# SCH_two-displays_2025-10-05.net
KiCad netlist of a schematic drawn in EasyEDA
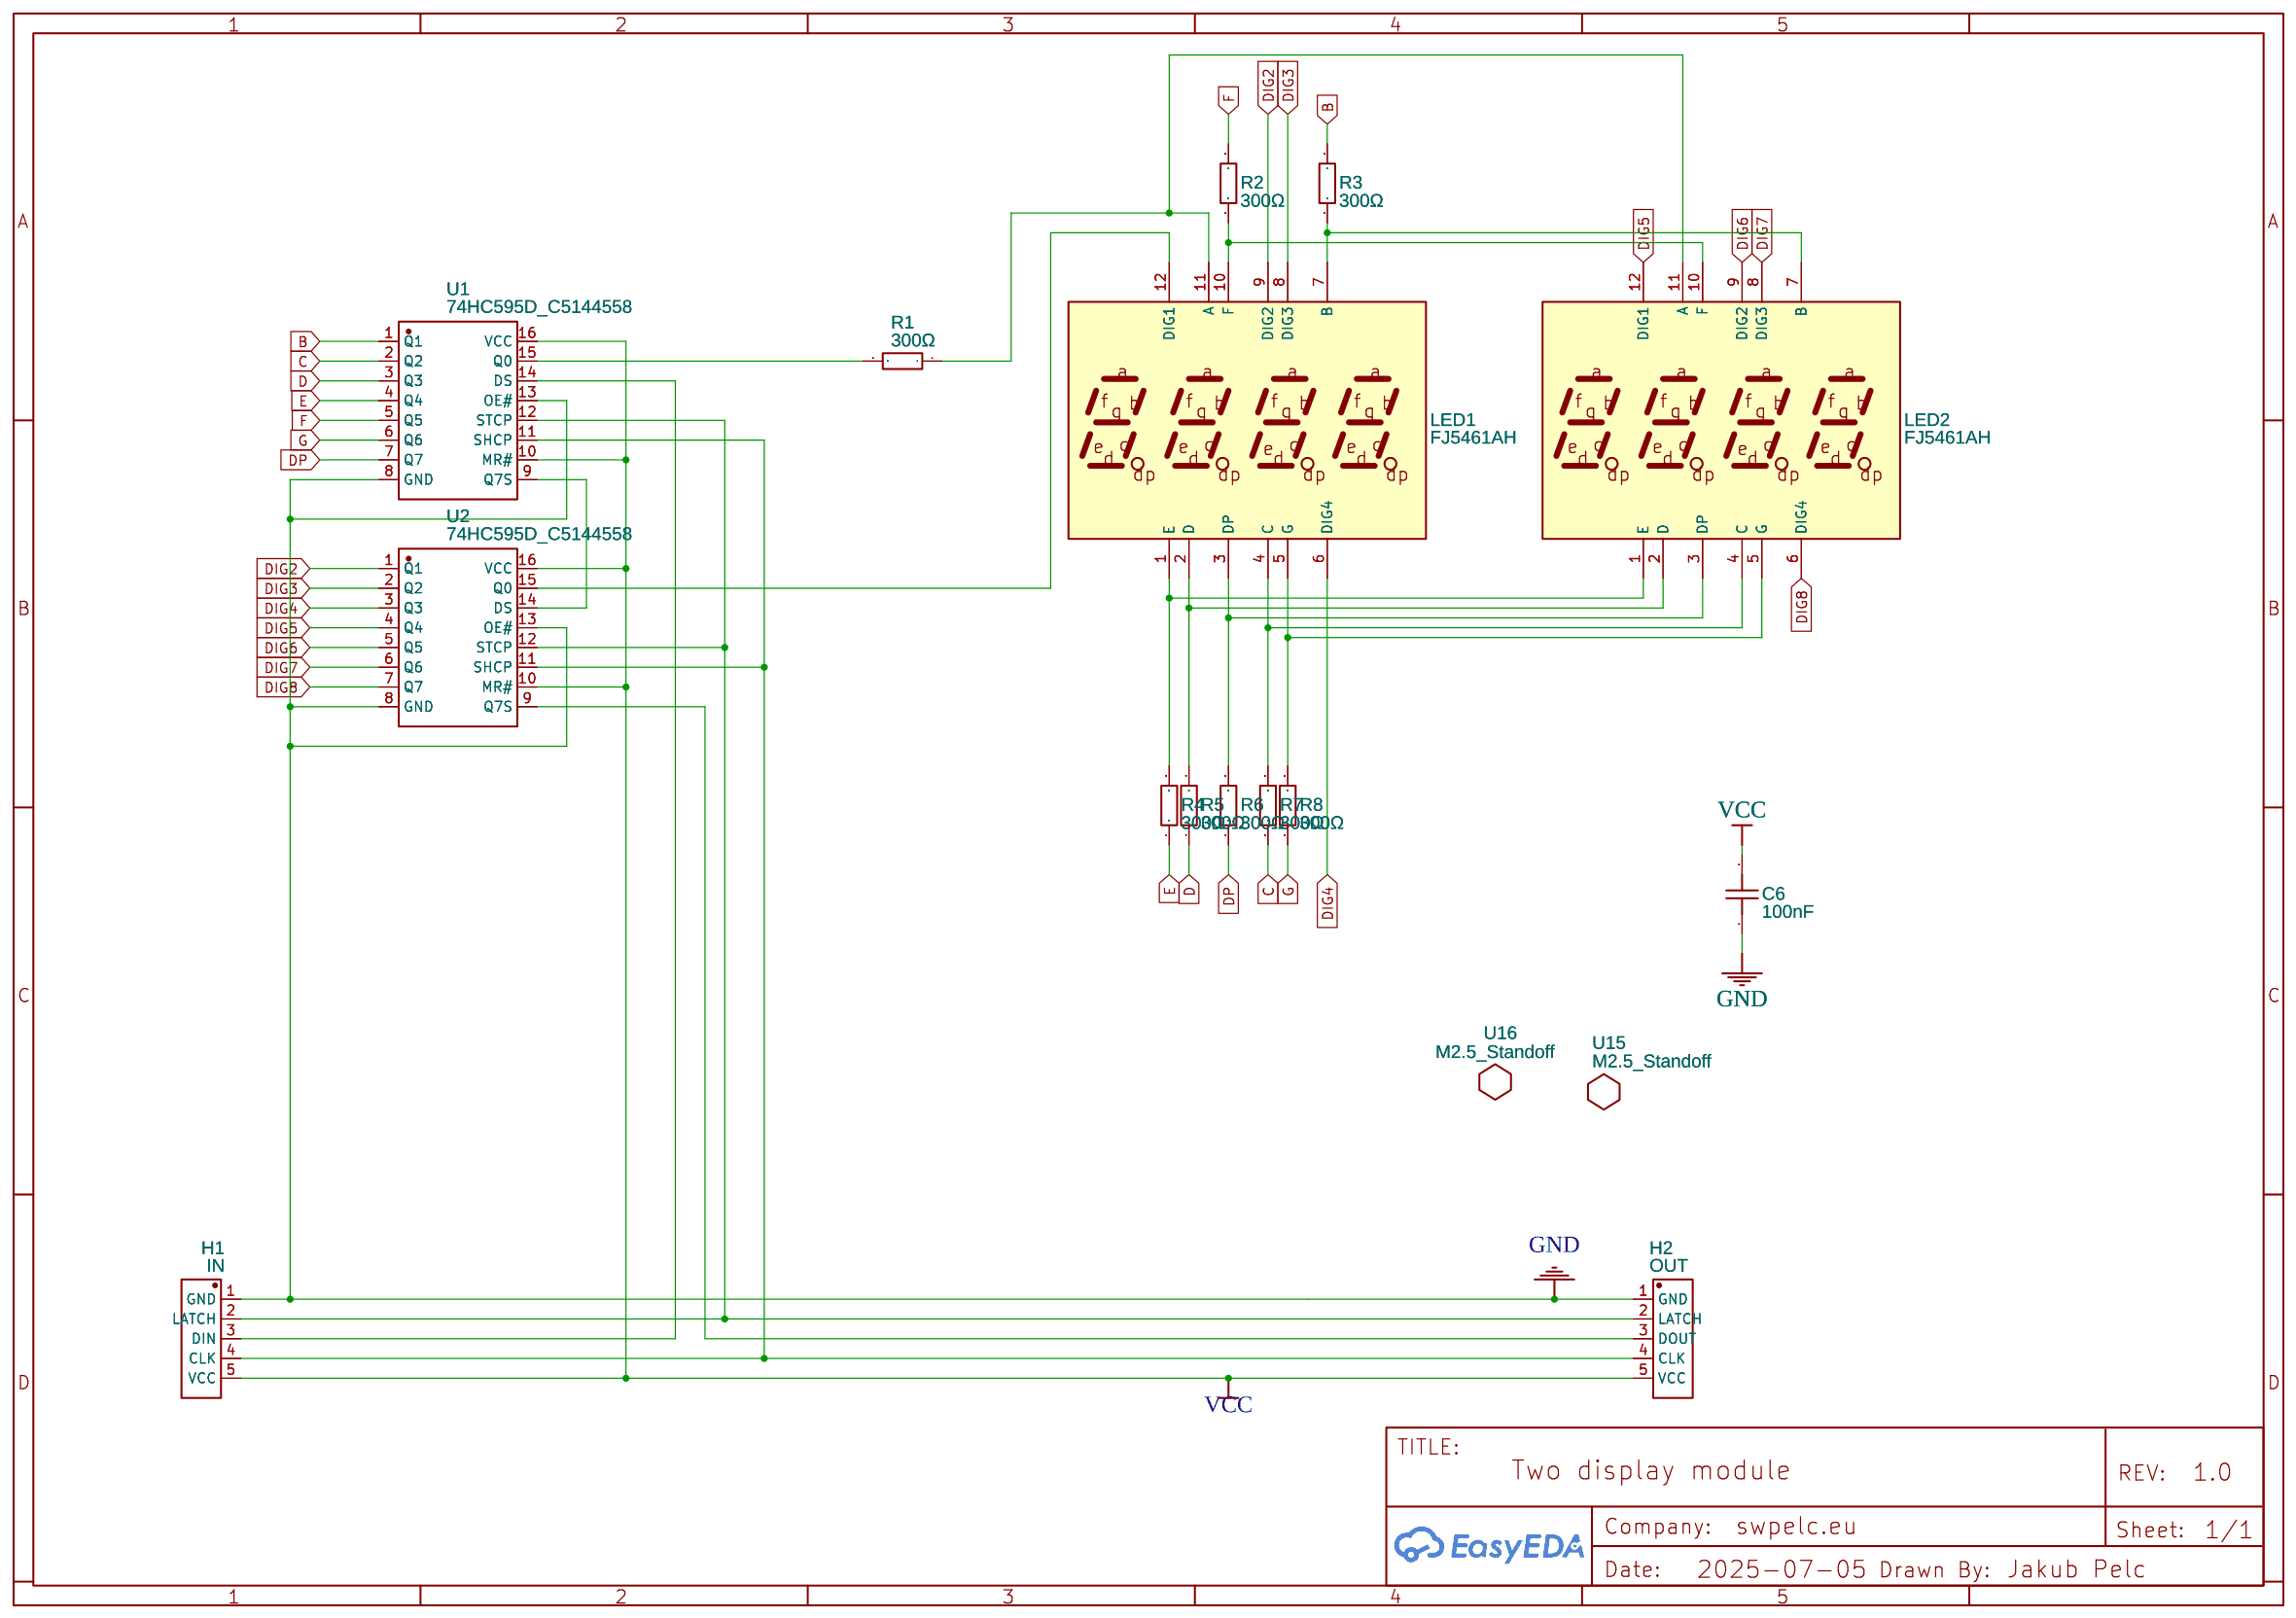
[diagram p0: schematic sheet]

(export (version "E")
  (design (tool "Eeschema 10.0.6"))
  (components
    (comp (ref "C6")
      (value "100nF")
      (fields
        (field (name "Manufacturer Part") "CC0603KRX7R9BB104")
        (field (name "Manufacturer") "YAGEO(国巨)")
      )
      (libsource (lib "") (part "CC0603KRX7R9BB104"))
    )
    (comp (ref "H1") (value "IN") (libsource (lib "") (part "HEADER - 2.54_1X5_1")))
    (comp (ref "H2") (value "OUT") (libsource (lib "") (part "HEADER - 2.54_1X5")))
    (comp (ref "LED1")
      (value "FJ5461AH")
      (fields (field (name "Manufacturer Part") "FJ5461AH 橙红") (field (name "Manufacturer") "志浩"))
      (libsource (lib "") (part "FJ5461AH"))
    )
    (comp (ref "LED2")
      (value "FJ5461AH")
      (fields (field (name "Manufacturer Part") "FJ5461AH 橙红") (field (name "Manufacturer") "志浩"))
      (libsource (lib "") (part "FJ5461AH"))
    )
    (comp (ref "R1")
      (value "300Ω")
      (fields (field (name "Manufacturer Part") "AR03DTC3000") (field (name "Manufacturer") "Viking(光颉)"))
      (libsource (lib "") (part "AR03DTC3000_1"))
    )
    (comp (ref "R2")
      (value "300Ω")
      (fields (field (name "Manufacturer Part") "AR03DTC3000") (field (name "Manufacturer") "Viking(光颉)"))
      (libsource (lib "") (part "AR03DTC3000"))
    )
    (comp (ref "R3")
      (value "300Ω")
      (fields (field (name "Manufacturer Part") "AR03DTC3000") (field (name "Manufacturer") "Viking(光颉)"))
      (libsource (lib "") (part "AR03DTC3000"))
    )
    (comp (ref "R4")
      (value "300Ω")
      (fields (field (name "Manufacturer Part") "AR03DTC3000") (field (name "Manufacturer") "Viking(光颉)"))
      (libsource (lib "") (part "AR03DTC3000"))
    )
    (comp (ref "R5")
      (value "300Ω")
      (fields (field (name "Manufacturer Part") "AR03DTC3000") (field (name "Manufacturer") "Viking(光颉)"))
      (libsource (lib "") (part "AR03DTC3000"))
    )
    (comp (ref "R6")
      (value "300Ω")
      (fields (field (name "Manufacturer Part") "AR03DTC3000") (field (name "Manufacturer") "Viking(光颉)"))
      (libsource (lib "") (part "AR03DTC3000"))
    )
    (comp (ref "R7")
      (value "300Ω")
      (fields (field (name "Manufacturer Part") "AR03DTC3000") (field (name "Manufacturer") "Viking(光颉)"))
      (libsource (lib "") (part "AR03DTC3000"))
    )
    (comp (ref "R8")
      (value "300Ω")
      (fields (field (name "Manufacturer Part") "AR03DTC3000") (field (name "Manufacturer") "Viking(光颉)"))
      (libsource (lib "") (part "AR03DTC3000"))
    )
    (comp (ref "U1")
      (value "74HC595D_C5144558")
      (fields (field (name "Manufacturer Part") "74HC595D") (field (name "Manufacturer") "JSMSEMI(杰盛微)"))
      (libsource (lib "") (part "74HC595D_C5144558"))
    )
    (comp (ref "U2")
      (value "74HC595D_C5144558")
      (fields (field (name "Manufacturer Part") "74HC595D") (field (name "Manufacturer") "JSMSEMI(杰盛微)"))
      (libsource (lib "") (part "74HC595D_C5144558"))
    )
    (comp (ref "U15") (value "M2.5_Standoff") (libsource (lib "") (part "M2.5_Standoff")))
    (comp (ref "U16") (value "M2.5_Standoff") (libsource (lib "") (part "M2.5_Standoff")))
  )
  (nets
    (net (code "1") (name "B") (class "Default")
      (node (ref "R3") (pin "2") (pinfunction "2_2") (pintype "unspecified"))
      (node (ref "U1") (pin "1") (pinfunction "Q1_1") (pintype "unspecified"))
    )
    (net (code "2") (name "C") (class "Default")
      (node (ref "R7") (pin "1") (pinfunction "1_1") (pintype "unspecified"))
      (node (ref "U1") (pin "2") (pinfunction "Q2_2") (pintype "unspecified"))
    )
    (net (code "3") (name "D") (class "Default")
      (node (ref "R5") (pin "1") (pinfunction "1_1") (pintype "unspecified"))
      (node (ref "U1") (pin "3") (pinfunction "Q3_3") (pintype "unspecified"))
    )
    (net (code "4") (name "DIG2") (class "Default")
      (node (ref "LED1") (pin "9") (pinfunction "DIG2_9") (pintype "input"))
      (node (ref "U2") (pin "1") (pinfunction "Q1_1") (pintype "unspecified"))
    )
    (net (code "5") (name "DIG3") (class "Default")
      (node (ref "LED1") (pin "8") (pinfunction "DIG3_8") (pintype "input"))
      (node (ref "U2") (pin "2") (pinfunction "Q2_2") (pintype "unspecified"))
    )
    (net (code "6") (name "DIG4") (class "Default")
      (node (ref "LED1") (pin "6") (pinfunction "DIG4_6") (pintype "input"))
      (node (ref "U2") (pin "3") (pinfunction "Q3_3") (pintype "unspecified"))
    )
    (net (code "7") (name "DIG5") (class "Default")
      (node (ref "LED2") (pin "12") (pinfunction "DIG1_12") (pintype "input"))
      (node (ref "U2") (pin "4") (pinfunction "Q4_4") (pintype "unspecified"))
    )
    (net (code "8") (name "DIG6") (class "Default")
      (node (ref "LED2") (pin "9") (pinfunction "DIG2_9") (pintype "input"))
      (node (ref "U2") (pin "5") (pinfunction "Q5_5") (pintype "unspecified"))
    )
    (net (code "9") (name "DIG7") (class "Default")
      (node (ref "LED2") (pin "8") (pinfunction "DIG3_8") (pintype "input"))
      (node (ref "U2") (pin "6") (pinfunction "Q6_6") (pintype "unspecified"))
    )
    (net (code "10") (name "DIG8") (class "Default")
      (node (ref "LED2") (pin "6") (pinfunction "DIG4_6") (pintype "input"))
      (node (ref "U2") (pin "7") (pinfunction "Q7_7") (pintype "unspecified"))
    )
    (net (code "11") (name "DP") (class "Default")
      (node (ref "R6") (pin "1") (pinfunction "1_1") (pintype "unspecified"))
      (node (ref "U1") (pin "7") (pinfunction "Q7_7") (pintype "unspecified"))
    )
    (net (code "12") (name "E") (class "Default")
      (node (ref "R4") (pin "1") (pinfunction "1_1") (pintype "unspecified"))
      (node (ref "U1") (pin "4") (pinfunction "Q4_4") (pintype "unspecified"))
    )
    (net (code "13") (name "F") (class "Default")
      (node (ref "R2") (pin "2") (pinfunction "2_2") (pintype "unspecified"))
      (node (ref "U1") (pin "5") (pinfunction "Q5_5") (pintype "unspecified"))
    )
    (net (code "14") (name "G") (class "Default")
      (node (ref "R8") (pin "1") (pinfunction "1_1") (pintype "unspecified"))
      (node (ref "U1") (pin "6") (pinfunction "Q6_6") (pintype "unspecified"))
    )
    (net (code "15") (name "GND") (class "Default")
      (node (ref "C6") (pin "1") (pinfunction "1_1") (pintype "unspecified"))
      (node (ref "H1") (pin "1") (pinfunction "GND_1") (pintype "unspecified"))
      (node (ref "H2") (pin "1") (pinfunction "GND_1") (pintype "unspecified"))
      (node (ref "U1") (pin "13") (pinfunction "OE#_13") (pintype "unspecified"))
      (node (ref "U1") (pin "8") (pinfunction "GND_8") (pintype "unspecified"))
      (node (ref "U2") (pin "13") (pinfunction "OE#_13") (pintype "unspecified"))
      (node (ref "U2") (pin "8") (pinfunction "GND_8") (pintype "unspecified"))
    )
    (net (code "16") (name "Net-(H1-CLK)") (class "Default")
      (node (ref "H1") (pin "4") (pinfunction "CLK_4") (pintype "unspecified"))
      (node (ref "H2") (pin "4") (pinfunction "CLK_4") (pintype "unspecified"))
      (node (ref "U1") (pin "11") (pinfunction "SHCP_11") (pintype "unspecified"))
      (node (ref "U2") (pin "11") (pinfunction "SHCP_11") (pintype "unspecified"))
    )
    (net (code "17") (name "Net-(H1-DIN)") (class "Default")
      (node (ref "H1") (pin "3") (pinfunction "DIN_3") (pintype "unspecified"))
      (node (ref "U1") (pin "14") (pinfunction "DS_14") (pintype "unspecified"))
    )
    (net (code "18") (name "Net-(H1-LATCH)") (class "Default")
      (node (ref "H1") (pin "2") (pinfunction "LATCH_2") (pintype "unspecified"))
      (node (ref "H2") (pin "2") (pinfunction "LATCH_2") (pintype "unspecified"))
      (node (ref "U1") (pin "12") (pinfunction "STCP_12") (pintype "unspecified"))
      (node (ref "U2") (pin "12") (pinfunction "STCP_12") (pintype "unspecified"))
    )
    (net (code "19") (name "Net-(H2-DOUT)") (class "Default")
      (node (ref "H2") (pin "3") (pinfunction "DOUT_3") (pintype "unspecified"))
      (node (ref "U2") (pin "9") (pinfunction "Q7S_9") (pintype "unspecified"))
    )
    (net (code "20") (name "Net-(LED1-A)") (class "Default")
      (node (ref "LED1") (pin "11") (pinfunction "A_11") (pintype "input"))
      (node (ref "LED2") (pin "11") (pinfunction "A_11") (pintype "input"))
      (node (ref "R1") (pin "1") (pinfunction "1_1") (pintype "unspecified"))
    )
    (net (code "21") (name "Net-(LED1-B)") (class "Default")
      (node (ref "LED1") (pin "7") (pinfunction "B_7") (pintype "input"))
      (node (ref "LED2") (pin "7") (pinfunction "B_7") (pintype "input"))
      (node (ref "R3") (pin "1") (pinfunction "1_1") (pintype "unspecified"))
    )
    (net (code "22") (name "Net-(LED1-C)") (class "Default")
      (node (ref "LED1") (pin "4") (pinfunction "C_4") (pintype "input"))
      (node (ref "LED2") (pin "4") (pinfunction "C_4") (pintype "input"))
      (node (ref "R7") (pin "2") (pinfunction "2_2") (pintype "unspecified"))
    )
    (net (code "23") (name "Net-(LED1-D)") (class "Default")
      (node (ref "LED1") (pin "2") (pinfunction "D_2") (pintype "input"))
      (node (ref "LED2") (pin "2") (pinfunction "D_2") (pintype "input"))
      (node (ref "R5") (pin "2") (pinfunction "2_2") (pintype "unspecified"))
    )
    (net (code "24") (name "Net-(LED1-DIG1)") (class "Default")
      (node (ref "LED1") (pin "12") (pinfunction "DIG1_12") (pintype "input"))
      (node (ref "U2") (pin "15") (pinfunction "Q0_15") (pintype "unspecified"))
    )
    (net (code "25") (name "Net-(LED1-DP)") (class "Default")
      (node (ref "LED1") (pin "3") (pinfunction "DP_3") (pintype "input"))
      (node (ref "LED2") (pin "3") (pinfunction "DP_3") (pintype "input"))
      (node (ref "R6") (pin "2") (pinfunction "2_2") (pintype "unspecified"))
    )
    (net (code "26") (name "Net-(LED1-E)") (class "Default")
      (node (ref "LED1") (pin "1") (pinfunction "E_1") (pintype "input"))
      (node (ref "LED2") (pin "1") (pinfunction "E_1") (pintype "input"))
      (node (ref "R4") (pin "2") (pinfunction "2_2") (pintype "unspecified"))
    )
    (net (code "27") (name "Net-(LED1-F)") (class "Default")
      (node (ref "LED1") (pin "10") (pinfunction "F_10") (pintype "input"))
      (node (ref "LED2") (pin "10") (pinfunction "F_10") (pintype "input"))
      (node (ref "R2") (pin "1") (pinfunction "1_1") (pintype "unspecified"))
    )
    (net (code "28") (name "Net-(LED1-G)") (class "Default")
      (node (ref "LED1") (pin "5") (pinfunction "G_5") (pintype "input"))
      (node (ref "LED2") (pin "5") (pinfunction "G_5") (pintype "input"))
      (node (ref "R8") (pin "2") (pinfunction "2_2") (pintype "unspecified"))
    )
    (net (code "29") (name "Net-(U1-Q0)") (class "Default")
      (node (ref "R1") (pin "2") (pinfunction "2_2") (pintype "unspecified"))
      (node (ref "U1") (pin "15") (pinfunction "Q0_15") (pintype "unspecified"))
    )
    (net (code "30") (name "Net-(U1-Q7S)") (class "Default")
      (node (ref "U1") (pin "9") (pinfunction "Q7S_9") (pintype "unspecified"))
      (node (ref "U2") (pin "14") (pinfunction "DS_14") (pintype "unspecified"))
    )
    (net (code "31") (name "VCC") (class "Default")
      (node (ref "C6") (pin "2") (pinfunction "2_2") (pintype "unspecified"))
      (node (ref "H1") (pin "5") (pinfunction "VCC_5") (pintype "unspecified"))
      (node (ref "H2") (pin "5") (pinfunction "VCC_5") (pintype "unspecified"))
      (node (ref "U1") (pin "10") (pinfunction "MR#_10") (pintype "unspecified"))
      (node (ref "U1") (pin "16") (pinfunction "VCC_16") (pintype "unspecified"))
      (node (ref "U2") (pin "10") (pinfunction "MR#_10") (pintype "unspecified"))
      (node (ref "U2") (pin "16") (pinfunction "VCC_16") (pintype "unspecified"))
    )
  )
)
